# IODevices.net
KiCad netlist of a schematic drawn in Altium Designer
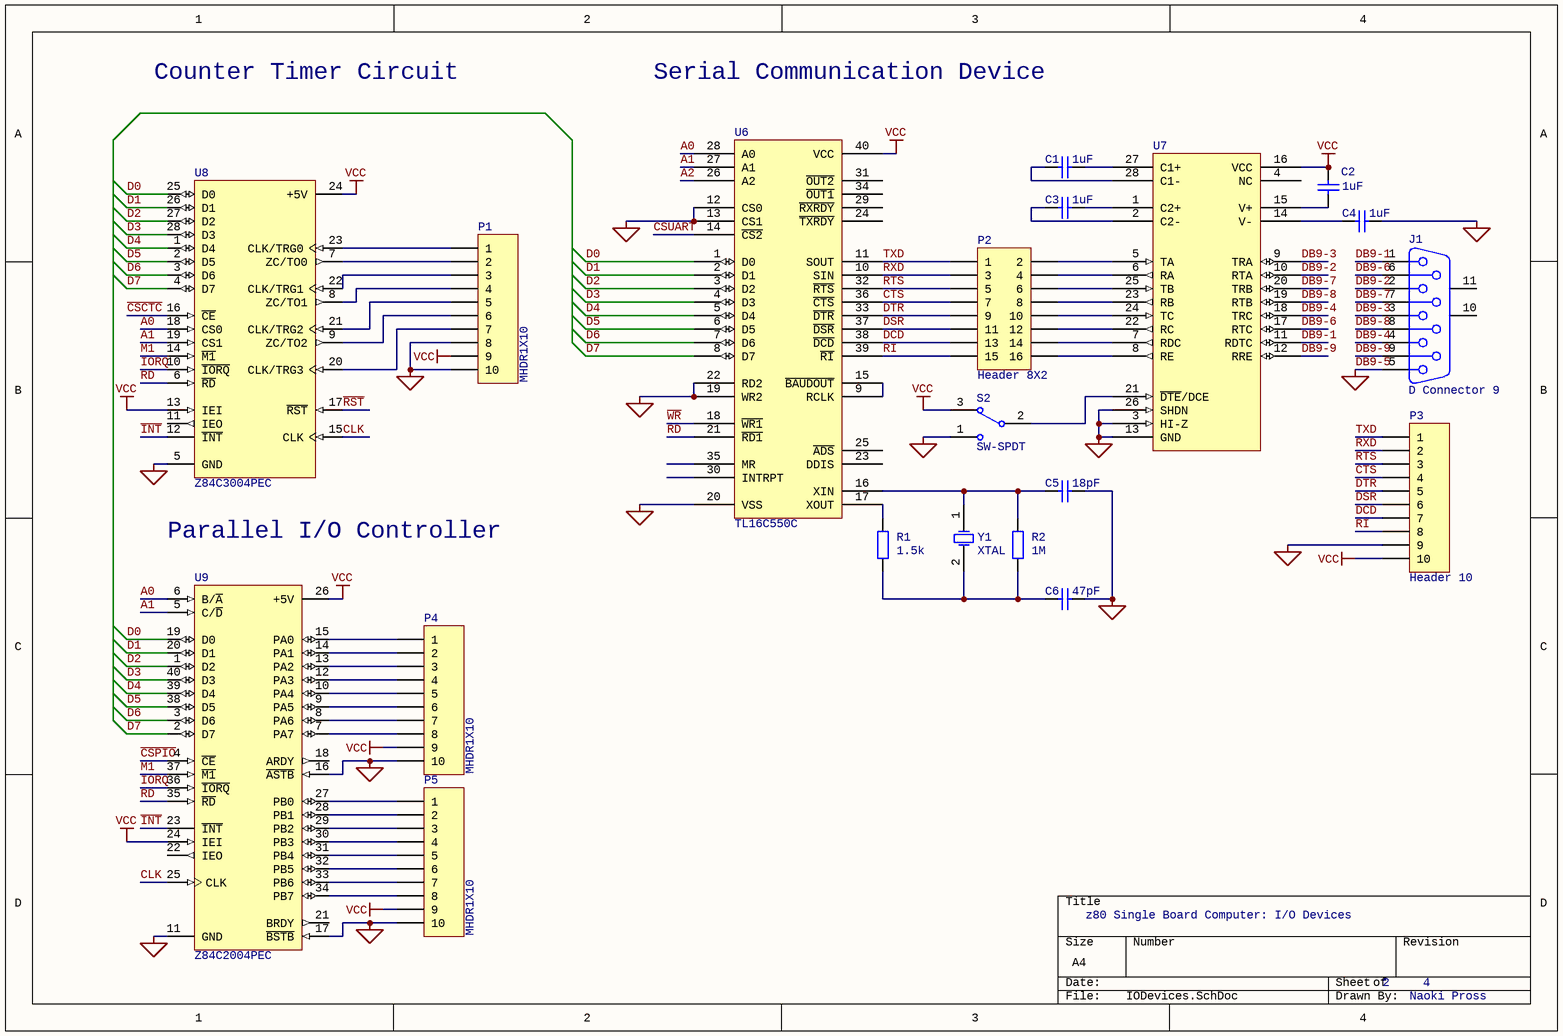
[diagram p0: IODevices.SchDoc]

(export (version "E")
  (design (tool "Eeschema 10.0.6"))
  (components
    (comp (ref "C1")
      (value "1uF")
      (footprint "RAD-0.3")
      (description "Capacitor")
      (fields (field (name "Comment") "Cap") (field (name "PUBLISHER") "Altium Limited"))
      (libsource (lib "z80uPC") (part "Cap"))
    )
    (comp (ref "C2")
      (value "1uF")
      (footprint "RAD-0.3")
      (description "Capacitor")
      (fields (field (name "Comment") "Cap") (field (name "PUBLISHER") "Altium Limited"))
      (libsource (lib "z80uPC") (part "Cap"))
    )
    (comp (ref "C3")
      (value "1uF")
      (footprint "RAD-0.3")
      (description "Capacitor")
      (fields (field (name "Comment") "Cap") (field (name "PUBLISHER") "Altium Limited"))
      (libsource (lib "z80uPC") (part "Cap"))
    )
    (comp (ref "C4")
      (value "1uF")
      (footprint "RAD-0.3")
      (description "Capacitor")
      (fields (field (name "Comment") "Cap") (field (name "PUBLISHER") "Altium Limited"))
      (libsource (lib "z80uPC") (part "Cap"))
    )
    (comp (ref "C5")
      (value "18pF")
      (footprint "RAD-0.1")
      (description "Capacitor")
      (fields (field (name "Comment") "Cap") (field (name "PUBLISHER") "Altium Limited"))
      (libsource (lib "z80uPC") (part "Cap"))
    )
    (comp (ref "C6")
      (value "47pF")
      (footprint "RAD-0.2")
      (description "Capacitor")
      (fields (field (name "Comment") "Cap") (field (name "PUBLISHER") "Altium Limited"))
      (libsource (lib "z80uPC") (part "Cap"))
    )
    (comp (ref "J1")
      (value "D Connector 9")
      (footprint "DSUB1.385-2H9")
      (description "Receptacle Assembly, 9 Position, Right Angle")
      (fields (field (name "PUBLISHER") "Altium Limited"))
      (libsource (lib "Miscellaneous Connectors") (part "D Connector 9"))
    )
    (comp (ref "P1")
      (value "MHDR1X10")
      (footprint "HDR5x2_SOCK")
      (description "Header, 10-Pin")
      (fields (field (name "PUBLISHER") "Altium Limited"))
      (libsource (lib "Miscellaneous Connectors") (part "MHDR1X10"))
    )
    (comp (ref "P2")
      (value "Header 8X2")
      (footprint "HDR2X8")
      (description "Header, 8-Pin, Dual row")
      (fields (field (name "PUBLISHER") "Altium Limited"))
      (libsource (lib "Miscellaneous Connectors") (part "Header 8X2"))
    )
    (comp (ref "P3")
      (value "Header 10")
      (footprint "HDR5x2_SOCK")
      (description "Header, 10-Pin")
      (fields (field (name "PUBLISHER") "Altium Limited"))
      (libsource (lib "Miscellaneous Connectors") (part "Header 10"))
    )
    (comp (ref "P4")
      (value "MHDR1X10")
      (footprint "HDR5x2_SOCK")
      (description "Header, 10-Pin")
      (fields (field (name "PUBLISHER") "Altium Limited"))
      (libsource (lib "Miscellaneous Connectors") (part "MHDR1X10"))
    )
    (comp (ref "P5")
      (value "MHDR1X10")
      (footprint "HDR5x2_SOCK")
      (description "Header, 10-Pin")
      (fields (field (name "PUBLISHER") "Altium Limited"))
      (libsource (lib "Miscellaneous Connectors") (part "MHDR1X10"))
    )
    (comp (ref "R1")
      (value "1.5k")
      (footprint "AXIAL-0.4")
      (description "Resistor")
      (fields (field (name "Comment") "Res2") (field (name "PUBLISHER") "Altium Limited"))
      (libsource (lib "z80uPC") (part "Res2"))
    )
    (comp (ref "R2")
      (value "1M")
      (footprint "AXIAL-0.4")
      (description "Resistor")
      (fields (field (name "Comment") "Res2") (field (name "PUBLISHER") "Altium Limited"))
      (libsource (lib "z80uPC") (part "Res2"))
    )
    (comp (ref "S2")
      (value "SW-SPDT")
      (footprint "SW_2WAY")
      (description "SPDT Subminiature Toggle Switch, Right Angle Mounting, Vertical Actuation")
      (fields (field (name "PUBLISHER") "Altium Limited"))
      (libsource (lib "Miscellaneous Devices") (part "SW-SPDT"))
    )
    (comp (ref "U6")
      (value "TL16C550C")
      (footprint "PLCC44_SOCKET")
      (libsource (lib "z80uPC") (part "TL16C550C"))
    )
    (comp (ref "U7") (value "MAX214") (footprint "DIP28W") (libsource (lib "z80uPC") (part "MAX214")))
    (comp (ref "U8")
      (value "Z84C3004PEC")
      (footprint "PDIP28")
      (description "CMOS Four-Channel Counter/Timer Circuit")
      (fields (field (name "PUBLISHER") "Altium Limited"))
      (libsource (lib "Zilog Logic Counter") (part "Z84C3004PEC"))
    )
    (comp (ref "U9")
      (value "Z84C2004PEC")
      (footprint "PDIP40")
      (description "CMOS Parallel I/O Controller")
      (fields (field (name "PUBLISHER") "Altium Limited"))
      (libsource (lib "Zilog Peripheral Interface") (part "Z84C2004PEC"))
    )
    (comp (ref "Y1")
      (value "XTAL")
      (footprint "RAD-0.2")
      (description "Crystal Oscillator")
      (fields (field (name "PUBLISHER") "Altium Limited"))
      (libsource (lib "Miscellaneous Devices") (part "XTAL"))
    )
  )
  (nets
    (net (code "1") (name "/A0") (class "Default")
      (node (ref "U6") (pin "28") (pinfunction "A0_28") (pintype "passive"))
      (node (ref "U8") (pin "18") (pinfunction "CS0_18") (pintype "input"))
      (node (ref "U9") (pin "6") (pinfunction "B/~{A}_6") (pintype "input"))
    )
    (net (code "2") (name "/A1") (class "Default")
      (node (ref "U6") (pin "27") (pinfunction "A1_27") (pintype "passive"))
      (node (ref "U8") (pin "19") (pinfunction "CS1_19") (pintype "input"))
      (node (ref "U9") (pin "5") (pinfunction "C/~{D}_5") (pintype "input"))
    )
    (net (code "3") (name "/A2") (class "Default")
      (node (ref "U6") (pin "26") (pinfunction "A2_26") (pintype "passive"))
    )
    (net (code "4") (name "/CLK") (class "Default")
      (node (ref "U8") (pin "15") (pinfunction "CLK_15") (pintype "input"))
      (node (ref "U9") (pin "25") (pinfunction "CLK_25") (pintype "input"))
    )
    (net (code "5") (name "/D0") (class "Default")
      (node (ref "U6") (pin "1") (pinfunction "D0_1") (pintype "bidirectional"))
      (node (ref "U8") (pin "25") (pinfunction "D0_25") (pintype "bidirectional"))
      (node (ref "U9") (pin "19") (pinfunction "D0_19") (pintype "bidirectional"))
    )
    (net (code "6") (name "/D1") (class "Default")
      (node (ref "U6") (pin "2") (pinfunction "D1_2") (pintype "bidirectional"))
      (node (ref "U8") (pin "26") (pinfunction "D1_26") (pintype "bidirectional"))
      (node (ref "U9") (pin "20") (pinfunction "D1_20") (pintype "bidirectional"))
    )
    (net (code "7") (name "/D2") (class "Default")
      (node (ref "U6") (pin "3") (pinfunction "D2_3") (pintype "bidirectional"))
      (node (ref "U8") (pin "27") (pinfunction "D2_27") (pintype "bidirectional"))
      (node (ref "U9") (pin "1") (pinfunction "D2_1") (pintype "bidirectional"))
    )
    (net (code "8") (name "/D3") (class "Default")
      (node (ref "U6") (pin "4") (pinfunction "D3_4") (pintype "bidirectional"))
      (node (ref "U8") (pin "28") (pinfunction "D3_28") (pintype "bidirectional"))
      (node (ref "U9") (pin "40") (pinfunction "D3_40") (pintype "bidirectional"))
    )
    (net (code "9") (name "/D4") (class "Default")
      (node (ref "U6") (pin "5") (pinfunction "D4_5") (pintype "bidirectional"))
      (node (ref "U8") (pin "1") (pinfunction "D4_1") (pintype "bidirectional"))
      (node (ref "U9") (pin "39") (pinfunction "D4_39") (pintype "bidirectional"))
    )
    (net (code "10") (name "/D5") (class "Default")
      (node (ref "U6") (pin "6") (pinfunction "D5_6") (pintype "bidirectional"))
      (node (ref "U8") (pin "2") (pinfunction "D5_2") (pintype "bidirectional"))
      (node (ref "U9") (pin "38") (pinfunction "D5_38") (pintype "bidirectional"))
    )
    (net (code "11") (name "/D6") (class "Default")
      (node (ref "U6") (pin "7") (pinfunction "D6_7") (pintype "bidirectional"))
      (node (ref "U8") (pin "3") (pinfunction "D6_3") (pintype "bidirectional"))
      (node (ref "U9") (pin "3") (pinfunction "D6_3") (pintype "bidirectional"))
    )
    (net (code "12") (name "/D7") (class "Default")
      (node (ref "U6") (pin "8") (pinfunction "D7_8") (pintype "bidirectional"))
      (node (ref "U8") (pin "4") (pinfunction "D7_4") (pintype "bidirectional"))
      (node (ref "U9") (pin "2") (pinfunction "D7_2") (pintype "bidirectional"))
    )
    (net (code "13") (name "/DB9-1") (class "Default")
      (node (ref "J1") (pin "1") (pinfunction "1_1") (pintype "passive"))
      (node (ref "U7") (pin "11") (pinfunction "RDTC_11") (pintype "bidirectional"))
    )
    (net (code "14") (name "/DB9-2") (class "Default")
      (node (ref "J1") (pin "2") (pinfunction "2_2") (pintype "passive"))
      (node (ref "U7") (pin "10") (pinfunction "RTA_10") (pintype "bidirectional"))
    )
    (net (code "15") (name "/DB9-3") (class "Default")
      (node (ref "J1") (pin "3") (pinfunction "3_3") (pintype "passive"))
      (node (ref "U7") (pin "9") (pinfunction "TRA_9") (pintype "bidirectional"))
    )
    (net (code "16") (name "/DB9-4") (class "Default")
      (node (ref "J1") (pin "4") (pinfunction "4_4") (pintype "passive"))
      (node (ref "U7") (pin "18") (pinfunction "TRC_18") (pintype "bidirectional"))
    )
    (net (code "17") (name "/DB9-6") (class "Default")
      (node (ref "J1") (pin "6") (pinfunction "6_6") (pintype "passive"))
      (node (ref "U7") (pin "17") (pinfunction "RTC_17") (pintype "bidirectional"))
    )
    (net (code "18") (name "/DB9-7") (class "Default")
      (node (ref "J1") (pin "7") (pinfunction "7_7") (pintype "passive"))
      (node (ref "U7") (pin "20") (pinfunction "TRB_20") (pintype "bidirectional"))
    )
    (net (code "19") (name "/DB9-8") (class "Default")
      (node (ref "J1") (pin "8") (pinfunction "8_8") (pintype "passive"))
      (node (ref "U7") (pin "19") (pinfunction "RTB_19") (pintype "bidirectional"))
    )
    (net (code "20") (name "/DB9-9") (class "Default")
      (node (ref "J1") (pin "9") (pinfunction "9_9") (pintype "passive"))
      (node (ref "U7") (pin "12") (pinfunction "RRE_12") (pintype "bidirectional"))
    )
    (net (code "21") (name "/RXD") (class "Default")
      (node (ref "P2") (pin "3") (pinfunction "3_3") (pintype "passive"))
      (node (ref "P3") (pin "2") (pinfunction "2_2") (pintype "passive"))
      (node (ref "U6") (pin "10") (pinfunction "SIN_10") (pintype "passive"))
    )
    (net (code "22") (name "/TXD") (class "Default")
      (node (ref "P2") (pin "1") (pinfunction "1_1") (pintype "passive"))
      (node (ref "P3") (pin "1") (pinfunction "1_1") (pintype "passive"))
      (node (ref "U6") (pin "11") (pinfunction "SOUT_11") (pintype "passive"))
    )
    (net (code "23") (name "/~{CSCTC}") (class "Default")
      (node (ref "U8") (pin "16") (pinfunction "~{CE}_16") (pintype "input"))
    )
    (net (code "24") (name "/~{CSPIO}") (class "Default")
      (node (ref "U9") (pin "4") (pinfunction "~{CE}_4") (pintype "input"))
    )
    (net (code "25") (name "/~{CSUART}") (class "Default")
      (node (ref "U6") (pin "14") (pinfunction "~{CS2}_14") (pintype "passive"))
    )
    (net (code "26") (name "/~{CTS}") (class "Default")
      (node (ref "P2") (pin "7") (pinfunction "7_7") (pintype "passive"))
      (node (ref "P3") (pin "4") (pinfunction "4_4") (pintype "passive"))
      (node (ref "U6") (pin "36") (pinfunction "~{CTS}_36") (pintype "passive"))
    )
    (net (code "27") (name "/~{DCD}") (class "Default")
      (node (ref "P2") (pin "13") (pinfunction "13_13") (pintype "passive"))
      (node (ref "P3") (pin "7") (pinfunction "7_7") (pintype "passive"))
      (node (ref "U6") (pin "38") (pinfunction "~{DCD}_38") (pintype "passive"))
    )
    (net (code "28") (name "/~{DSR}") (class "Default")
      (node (ref "P2") (pin "11") (pinfunction "11_11") (pintype "passive"))
      (node (ref "P3") (pin "6") (pinfunction "6_6") (pintype "passive"))
      (node (ref "U6") (pin "37") (pinfunction "~{DSR}_37") (pintype "passive"))
    )
    (net (code "29") (name "/~{DTR}") (class "Default")
      (node (ref "P2") (pin "9") (pinfunction "9_9") (pintype "passive"))
      (node (ref "P3") (pin "5") (pinfunction "5_5") (pintype "passive"))
      (node (ref "U6") (pin "33") (pinfunction "~{DTR}_33") (pintype "passive"))
    )
    (net (code "30") (name "/~{INT}") (class "Default")
      (node (ref "U8") (pin "12") (pinfunction "~{INT}_12") (pintype "open_collector"))
      (node (ref "U9") (pin "23") (pinfunction "~{INT}_23") (pintype "open_collector"))
    )
    (net (code "31") (name "/~{IORQ}") (class "Default")
      (node (ref "U8") (pin "10") (pinfunction "~{IORQ}_10") (pintype "input"))
      (node (ref "U9") (pin "36") (pinfunction "~{IORQ}_36") (pintype "input"))
    )
    (net (code "32") (name "/~{M1}") (class "Default")
      (node (ref "U8") (pin "14") (pinfunction "~{M1}_14") (pintype "input"))
      (node (ref "U9") (pin "37") (pinfunction "~{M1}_37") (pintype "input"))
    )
    (net (code "33") (name "/~{RD}") (class "Default")
      (node (ref "U6") (pin "21") (pinfunction "~{RD1}_21") (pintype "passive"))
      (node (ref "U8") (pin "6") (pinfunction "~{RD}_6") (pintype "input"))
      (node (ref "U9") (pin "35") (pinfunction "~{RD}_35") (pintype "input"))
    )
    (net (code "34") (name "/~{RI}") (class "Default")
      (node (ref "P2") (pin "15") (pinfunction "15_15") (pintype "passive"))
      (node (ref "P3") (pin "8") (pinfunction "8_8") (pintype "passive"))
      (node (ref "U6") (pin "39") (pinfunction "~{RI}_39") (pintype "passive"))
    )
    (net (code "35") (name "/~{RST}") (class "Default")
      (node (ref "U8") (pin "17") (pinfunction "~{RST}_17") (pintype "input"))
    )
    (net (code "36") (name "/~{RTS}") (class "Default")
      (node (ref "P2") (pin "5") (pinfunction "5_5") (pintype "passive"))
      (node (ref "P3") (pin "3") (pinfunction "3_3") (pintype "passive"))
      (node (ref "U6") (pin "32") (pinfunction "~{RTS}_32") (pintype "passive"))
    )
    (net (code "37") (name "/~{WR}") (class "Default")
      (node (ref "U6") (pin "18") (pinfunction "~{WR1}_18") (pintype "passive"))
    )
    (net (code "38") (name "GND") (class "Default")
      (node (ref "C4") (pin "2") (pinfunction "2_2") (pintype "passive"))
      (node (ref "C5") (pin "2") (pinfunction "2_2") (pintype "passive"))
      (node (ref "C6") (pin "2") (pinfunction "2_2") (pintype "passive"))
      (node (ref "J1") (pin "5") (pinfunction "5_5") (pintype "passive"))
      (node (ref "P1") (pin "10") (pinfunction "10_10") (pintype "passive"))
      (node (ref "P1") (pin "8") (pinfunction "8_8") (pintype "passive"))
      (node (ref "P3") (pin "9") (pinfunction "9_9") (pintype "passive"))
      (node (ref "P4") (pin "10") (pinfunction "10_10") (pintype "passive"))
      (node (ref "P5") (pin "10") (pinfunction "10_10") (pintype "passive"))
      (node (ref "S2") (pin "1") (pinfunction "1_1") (pintype "passive"))
      (node (ref "U6") (pin "12") (pinfunction "CS0_12") (pintype "passive"))
      (node (ref "U6") (pin "13") (pinfunction "CS1_13") (pintype "passive"))
      (node (ref "U6") (pin "19") (pinfunction "WR2_19") (pintype "passive"))
      (node (ref "U6") (pin "20") (pinfunction "VSS_20") (pintype "power_in"))
      (node (ref "U6") (pin "22") (pinfunction "RD2_22") (pintype "passive"))
      (node (ref "U7") (pin "13") (pinfunction "GND_13") (pintype "passive"))
      (node (ref "U7") (pin "26") (pinfunction "SHDN_26") (pintype "input"))
      (node (ref "U7") (pin "3") (pinfunction "HI-Z_3") (pintype "input"))
      (node (ref "U8") (pin "5") (pinfunction "GND_5") (pintype "power_in"))
      (node (ref "U9") (pin "11") (pinfunction "GND_11") (pintype "power_in"))
      (node (ref "U9") (pin "16") (pinfunction "~{ASTB}_16") (pintype "input"))
      (node (ref "U9") (pin "17") (pinfunction "~{BSTB}_17") (pintype "input"))
    )
    (net (code "39") (name "Net-(U6-RCLK)") (class "Default")
      (node (ref "U6") (pin "15") (pinfunction "~{BAUDOUT}_15") (pintype "passive"))
      (node (ref "U6") (pin "9") (pinfunction "RCLK_9") (pintype "passive"))
    )
    (net (code "40") (name "Net-(U6-XIN)") (class "Default")
      (node (ref "C5") (pin "1") (pinfunction "1_1") (pintype "passive"))
      (node (ref "R2") (pin "2") (pinfunction "2_2") (pintype "passive"))
      (node (ref "U6") (pin "16") (pinfunction "XIN_16") (pintype "passive"))
      (node (ref "Y1") (pin "1") (pinfunction "OSC1_1") (pintype "passive"))
    )
    (net (code "41") (name "Net-(U6-XOUT)") (class "Default")
      (node (ref "R1") (pin "2") (pinfunction "2_2") (pintype "passive"))
      (node (ref "U6") (pin "17") (pinfunction "XOUT_17") (pintype "passive"))
    )
    (net (code "42") (name "Net-(U7-C1+)") (class "Default")
      (node (ref "C1") (pin "2") (pinfunction "2_2") (pintype "passive"))
      (node (ref "U7") (pin "27") (pinfunction "C1+_27") (pintype "passive"))
    )
    (net (code "43") (name "Net-(U7-C1-)") (class "Default")
      (node (ref "C1") (pin "1") (pinfunction "1_1") (pintype "passive"))
      (node (ref "U7") (pin "28") (pinfunction "C1-_28") (pintype "passive"))
    )
    (net (code "44") (name "Net-(U7-C2+)") (class "Default")
      (node (ref "C3") (pin "2") (pinfunction "2_2") (pintype "passive"))
      (node (ref "U7") (pin "1") (pinfunction "C2+_1") (pintype "passive"))
    )
    (net (code "45") (name "Net-(U7-C2-)") (class "Default")
      (node (ref "C3") (pin "1") (pinfunction "1_1") (pintype "passive"))
      (node (ref "U7") (pin "2") (pinfunction "C2-_2") (pintype "passive"))
    )
    (net (code "46") (name "Net-(U7-RA)") (class "Default")
      (node (ref "P2") (pin "4") (pinfunction "4_4") (pintype "passive"))
      (node (ref "U7") (pin "6") (pinfunction "RA_6") (pintype "output"))
    )
    (net (code "47") (name "Net-(U7-RB)") (class "Default")
      (node (ref "P2") (pin "8") (pinfunction "8_8") (pintype "passive"))
      (node (ref "U7") (pin "23") (pinfunction "RB_23") (pintype "output"))
    )
    (net (code "48") (name "Net-(U7-RC)") (class "Default")
      (node (ref "P2") (pin "12") (pinfunction "12_12") (pintype "passive"))
      (node (ref "U7") (pin "22") (pinfunction "RC_22") (pintype "output"))
    )
    (net (code "49") (name "Net-(U7-RDC)") (class "Default")
      (node (ref "P2") (pin "14") (pinfunction "14_14") (pintype "passive"))
      (node (ref "U7") (pin "7") (pinfunction "RDC_7") (pintype "output"))
    )
    (net (code "50") (name "Net-(U7-RE)") (class "Default")
      (node (ref "P2") (pin "16") (pinfunction "16_16") (pintype "passive"))
      (node (ref "U7") (pin "8") (pinfunction "RE_8") (pintype "output"))
    )
    (net (code "51") (name "Net-(U7-TA)") (class "Default")
      (node (ref "P2") (pin "2") (pinfunction "2_2") (pintype "passive"))
      (node (ref "U7") (pin "5") (pinfunction "TA_5") (pintype "input"))
    )
    (net (code "52") (name "Net-(U7-TB)") (class "Default")
      (node (ref "P2") (pin "6") (pinfunction "6_6") (pintype "passive"))
      (node (ref "U7") (pin "25") (pinfunction "TB_25") (pintype "input"))
    )
    (net (code "53") (name "Net-(U7-TC)") (class "Default")
      (node (ref "P2") (pin "10") (pinfunction "10_10") (pintype "passive"))
      (node (ref "U7") (pin "24") (pinfunction "TC_24") (pintype "input"))
    )
    (net (code "54") (name "Net-(U7-V+)") (class "Default")
      (node (ref "C2") (pin "1") (pinfunction "1_1") (pintype "passive"))
      (node (ref "U7") (pin "15") (pinfunction "V+_15") (pintype "passive"))
    )
    (net (code "55") (name "Net-(U7-V-)") (class "Default")
      (node (ref "C4") (pin "1") (pinfunction "1_1") (pintype "passive"))
      (node (ref "U7") (pin "14") (pinfunction "V-_14") (pintype "passive"))
    )
    (net (code "56") (name "Net-(U7-~{DTE}{slash}DCE)") (class "Default")
      (node (ref "S2") (pin "2") (pinfunction "2_2") (pintype "passive"))
      (node (ref "U7") (pin "21") (pinfunction "~{DTE}/DCE_21") (pintype "input"))
    )
    (net (code "57") (name "Net-(U8-CLK{slash}TRG0)") (class "Default")
      (node (ref "P1") (pin "1") (pinfunction "1_1") (pintype "passive"))
      (node (ref "U8") (pin "23") (pinfunction "CLK/TRG0_23") (pintype "input"))
    )
    (net (code "58") (name "Net-(U8-CLK{slash}TRG1)") (class "Default")
      (node (ref "P1") (pin "3") (pinfunction "3_3") (pintype "passive"))
      (node (ref "U8") (pin "22") (pinfunction "CLK/TRG1_22") (pintype "input"))
    )
    (net (code "59") (name "Net-(U8-CLK{slash}TRG2)") (class "Default")
      (node (ref "P1") (pin "5") (pinfunction "5_5") (pintype "passive"))
      (node (ref "U8") (pin "21") (pinfunction "CLK/TRG2_21") (pintype "input"))
    )
    (net (code "60") (name "Net-(U8-CLK{slash}TRG3)") (class "Default")
      (node (ref "P1") (pin "7") (pinfunction "7_7") (pintype "passive"))
      (node (ref "U8") (pin "20") (pinfunction "CLK/TRG3_20") (pintype "input"))
    )
    (net (code "61") (name "Net-(U8-ZC{slash}TO0)") (class "Default")
      (node (ref "P1") (pin "2") (pinfunction "2_2") (pintype "passive"))
      (node (ref "U8") (pin "7") (pinfunction "ZC/TO0_7") (pintype "output"))
    )
    (net (code "62") (name "Net-(U8-ZC{slash}TO1)") (class "Default")
      (node (ref "P1") (pin "4") (pinfunction "4_4") (pintype "passive"))
      (node (ref "U8") (pin "8") (pinfunction "ZC/TO1_8") (pintype "output"))
    )
    (net (code "63") (name "Net-(U8-ZC{slash}TO2)") (class "Default")
      (node (ref "P1") (pin "6") (pinfunction "6_6") (pintype "passive"))
      (node (ref "U8") (pin "9") (pinfunction "ZC/TO2_9") (pintype "output"))
    )
    (net (code "64") (name "Net-(U9-PA0)") (class "Default")
      (node (ref "P4") (pin "1") (pinfunction "1_1") (pintype "passive"))
      (node (ref "U9") (pin "15") (pinfunction "PA0_15") (pintype "bidirectional"))
    )
    (net (code "65") (name "Net-(U9-PA1)") (class "Default")
      (node (ref "P4") (pin "2") (pinfunction "2_2") (pintype "passive"))
      (node (ref "U9") (pin "14") (pinfunction "PA1_14") (pintype "bidirectional"))
    )
    (net (code "66") (name "Net-(U9-PA2)") (class "Default")
      (node (ref "P4") (pin "3") (pinfunction "3_3") (pintype "passive"))
      (node (ref "U9") (pin "13") (pinfunction "PA2_13") (pintype "bidirectional"))
    )
    (net (code "67") (name "Net-(U9-PA3)") (class "Default")
      (node (ref "P4") (pin "4") (pinfunction "4_4") (pintype "passive"))
      (node (ref "U9") (pin "12") (pinfunction "PA3_12") (pintype "bidirectional"))
    )
    (net (code "68") (name "Net-(U9-PA4)") (class "Default")
      (node (ref "P4") (pin "5") (pinfunction "5_5") (pintype "passive"))
      (node (ref "U9") (pin "10") (pinfunction "PA4_10") (pintype "bidirectional"))
    )
    (net (code "69") (name "Net-(U9-PA5)") (class "Default")
      (node (ref "P4") (pin "6") (pinfunction "6_6") (pintype "passive"))
      (node (ref "U9") (pin "9") (pinfunction "PA5_9") (pintype "bidirectional"))
    )
    (net (code "70") (name "Net-(U9-PA6)") (class "Default")
      (node (ref "P4") (pin "7") (pinfunction "7_7") (pintype "passive"))
      (node (ref "U9") (pin "8") (pinfunction "PA6_8") (pintype "bidirectional"))
    )
    (net (code "71") (name "Net-(U9-PA7)") (class "Default")
      (node (ref "P4") (pin "8") (pinfunction "8_8") (pintype "passive"))
      (node (ref "U9") (pin "7") (pinfunction "PA7_7") (pintype "bidirectional"))
    )
    (net (code "72") (name "Net-(U9-PB0)") (class "Default")
      (node (ref "P5") (pin "1") (pinfunction "1_1") (pintype "passive"))
      (node (ref "U9") (pin "27") (pinfunction "PB0_27") (pintype "bidirectional"))
    )
    (net (code "73") (name "Net-(U9-PB1)") (class "Default")
      (node (ref "P5") (pin "2") (pinfunction "2_2") (pintype "passive"))
      (node (ref "U9") (pin "28") (pinfunction "PB1_28") (pintype "bidirectional"))
    )
    (net (code "74") (name "Net-(U9-PB2)") (class "Default")
      (node (ref "P5") (pin "3") (pinfunction "3_3") (pintype "passive"))
      (node (ref "U9") (pin "29") (pinfunction "PB2_29") (pintype "bidirectional"))
    )
    (net (code "75") (name "Net-(U9-PB3)") (class "Default")
      (node (ref "P5") (pin "4") (pinfunction "4_4") (pintype "passive"))
      (node (ref "U9") (pin "30") (pinfunction "PB3_30") (pintype "bidirectional"))
    )
    (net (code "76") (name "Net-(U9-PB4)") (class "Default")
      (node (ref "P5") (pin "5") (pinfunction "5_5") (pintype "passive"))
      (node (ref "U9") (pin "31") (pinfunction "PB4_31") (pintype "bidirectional"))
    )
    (net (code "77") (name "Net-(U9-PB5)") (class "Default")
      (node (ref "P5") (pin "6") (pinfunction "6_6") (pintype "passive"))
      (node (ref "U9") (pin "32") (pinfunction "PB5_32") (pintype "bidirectional"))
    )
    (net (code "78") (name "Net-(U9-PB6)") (class "Default")
      (node (ref "P5") (pin "7") (pinfunction "7_7") (pintype "passive"))
      (node (ref "U9") (pin "33") (pinfunction "PB6_33") (pintype "bidirectional"))
    )
    (net (code "79") (name "Net-(U9-PB7)") (class "Default")
      (node (ref "P5") (pin "8") (pinfunction "8_8") (pintype "passive"))
      (node (ref "U9") (pin "34") (pinfunction "PB7_34") (pintype "bidirectional"))
    )
    (net (code "80") (name "Net-(Y1-OSC2)") (class "Default")
      (node (ref "C6") (pin "1") (pinfunction "1_1") (pintype "passive"))
      (node (ref "R1") (pin "1") (pinfunction "1_1") (pintype "passive"))
      (node (ref "R2") (pin "1") (pinfunction "1_1") (pintype "passive"))
      (node (ref "Y1") (pin "2") (pinfunction "OSC2_2") (pintype "passive"))
    )
    (net (code "81") (name "VCC") (class "Default")
      (node (ref "C2") (pin "2") (pinfunction "2_2") (pintype "passive"))
      (node (ref "P1") (pin "9") (pinfunction "9_9") (pintype "passive"))
      (node (ref "P3") (pin "10") (pinfunction "10_10") (pintype "passive"))
      (node (ref "P4") (pin "9") (pinfunction "9_9") (pintype "passive"))
      (node (ref "P5") (pin "9") (pinfunction "9_9") (pintype "passive"))
      (node (ref "S2") (pin "3") (pinfunction "3_3") (pintype "passive"))
      (node (ref "U6") (pin "40") (pinfunction "VCC_40") (pintype "passive"))
      (node (ref "U7") (pin "16") (pinfunction "VCC_16") (pintype "passive"))
      (node (ref "U8") (pin "13") (pinfunction "IEI_13") (pintype "input"))
      (node (ref "U8") (pin "24") (pinfunction "+5V_24") (pintype "power_in"))
      (node (ref "U9") (pin "24") (pinfunction "IEI_24") (pintype "input"))
      (node (ref "U9") (pin "26") (pinfunction "+5V_26") (pintype "power_in"))
    )
    (net (code "82") (name "unconnected-(J1-MH1-Pad10)") (class "Default")
      (node (ref "J1") (pin "10") (pinfunction "MH1_10") (pintype "passive"))
    )
    (net (code "83") (name "unconnected-(J1-MH2-Pad11)") (class "Default")
      (node (ref "J1") (pin "11") (pinfunction "MH2_11") (pintype "passive"))
    )
    (net (code "84") (name "unconnected-(U6-DDIS-Pad23)") (class "Default")
      (node (ref "U6") (pin "23") (pinfunction "DDIS_23") (pintype "passive"))
    )
    (net (code "85") (name "unconnected-(U6-INTRPT-Pad30)") (class "Default")
      (node (ref "U6") (pin "30") (pinfunction "INTRPT_30") (pintype "passive"))
    )
    (net (code "86") (name "unconnected-(U6-MR-Pad35)") (class "Default")
      (node (ref "U6") (pin "35") (pinfunction "MR_35") (pintype "passive"))
    )
    (net (code "87") (name "unconnected-(U6-~{ADS}-Pad25)") (class "Default")
      (node (ref "U6") (pin "25") (pinfunction "~{ADS}_25") (pintype "passive"))
    )
    (net (code "88") (name "unconnected-(U6-~{OUT1}-Pad34)") (class "Default")
      (node (ref "U6") (pin "34") (pinfunction "~{OUT1}_34") (pintype "passive"))
    )
    (net (code "89") (name "unconnected-(U6-~{OUT2}-Pad31)") (class "Default")
      (node (ref "U6") (pin "31") (pinfunction "~{OUT2}_31") (pintype "passive"))
    )
    (net (code "90") (name "unconnected-(U6-~{RXRDY}-Pad29)") (class "Default")
      (node (ref "U6") (pin "29") (pinfunction "~{RXRDY}_29") (pintype "passive"))
    )
    (net (code "91") (name "unconnected-(U6-~{TXRDY}-Pad24)") (class "Default")
      (node (ref "U6") (pin "24") (pinfunction "~{TXRDY}_24") (pintype "passive"))
    )
    (net (code "92") (name "unconnected-(U7-NC-Pad4)") (class "Default")
      (node (ref "U7") (pin "4") (pinfunction "NC_4") (pintype "passive"))
    )
    (net (code "93") (name "unconnected-(U8-IEO-Pad11)") (class "Default")
      (node (ref "U8") (pin "11") (pinfunction "IEO_11") (pintype "output"))
    )
    (net (code "94") (name "unconnected-(U9-ARDY-Pad18)") (class "Default")
      (node (ref "U9") (pin "18") (pinfunction "ARDY_18") (pintype "output"))
    )
    (net (code "95") (name "unconnected-(U9-BRDY-Pad21)") (class "Default")
      (node (ref "U9") (pin "21") (pinfunction "BRDY_21") (pintype "output"))
    )
    (net (code "96") (name "unconnected-(U9-IEO-Pad22)") (class "Default")
      (node (ref "U9") (pin "22") (pinfunction "IEO_22") (pintype "output"))
    )
  )
)
